# 18_-WIFI_MODULE.net
KiCad netlist of a schematic drawn in Altium Designer
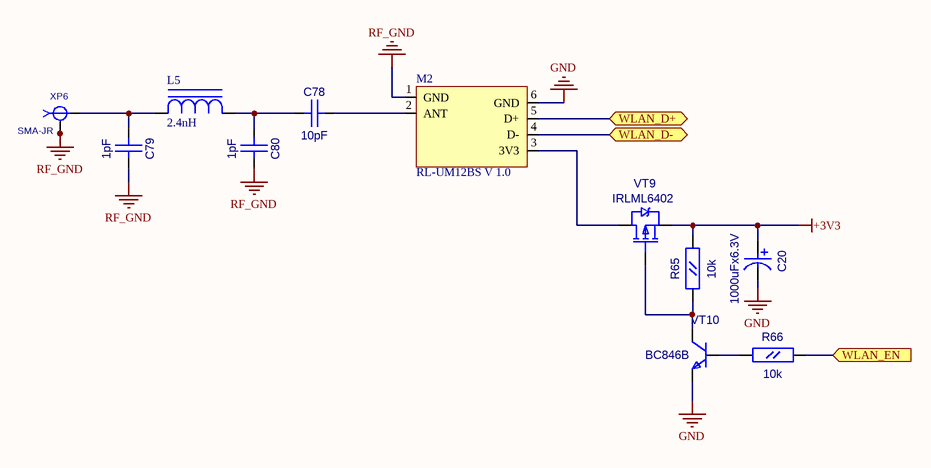
[diagram p0: [18]-WIFI_MODULE.SchDoc]

(export (version "E")
  (design (tool "Eeschema 10.0.6"))
  (components
    (comp (ref "C20")
      (value "1000uFx6.3V")
      (footprint "CC8X3.5")
      (description "Radial capacitor")
      (libsource (lib "fizik_lib (1)") (part "CAP_8mm"))
    )
    (comp (ref "C78")
      (value "10pF")
      (footprint "CC0603")
      (description "CC0603")
      (libsource (lib "gprs_modem_2") (part "CC0603"))
    )
    (comp (ref "C79")
      (value "1pF")
      (footprint "CC0603")
      (description "CC0603")
      (libsource (lib "gprs_modem_2") (part "CC0603"))
    )
    (comp (ref "C80")
      (value "1pF")
      (footprint "CC0603")
      (description "CC0603")
      (libsource (lib "gprs_modem_2") (part "CC0603"))
    )
    (comp (ref "L5")
      (value "2.4nH")
      (footprint "L0402")
      (description "L0402")
      (libsource (lib "gprs_modem_2") (part "L0402"))
    )
    (comp (ref "M2")
      (value "RL-UM12BS V 1.0")
      (footprint "RTL8188_MODULE")
      (libsource (lib "fizik_lib") (part "RTL8188_MODULE"))
    )
    (comp (ref "R65")
      (value "10k")
      (footprint "RC0603")
      (description "RC0603")
      (libsource (lib "gprs_modem_2") (part "RC0603"))
    )
    (comp (ref "R66")
      (value "10k")
      (footprint "RC0603")
      (description "RC0603")
      (libsource (lib "gprs_modem_2") (part "RC0603"))
    )
    (comp (ref "VT9")
      (value "IRLML6402")
      (footprint "SOT-23(123)")
      (description "HEXFET Power MOSFET")
      (libsource (lib "gprs_modem_2") (part "IRLML6402"))
    )
    (comp (ref "VT10")
      (value "BC846B")
      (footprint "SOT-23(123)")
      (description "BC846BLT1")
      (libsource (lib "gprs_modem_2") (part "BC846BLT1"))
    )
    (comp (ref "XP6") (value "SMA-JR") (footprint "SMA-JR") (libsource (lib "fizik_lib") (part "SMA-JR")))
  )
  (nets
    (net (code "1") (name "+3V3") (class "Default")
      (node (ref "C20") (pin "1") (pintype "passive"))
      (node (ref "R65") (pin "2") (pinfunction "B_2") (pintype "passive"))
      (node (ref "VT9") (pin "2") (pinfunction "S_2") (pintype "passive"))
    )
    (net (code "2") (name "/WLAN_D+") (class "Default")
      (node (ref "M2") (pin "5") (pinfunction "D+_5") (pintype "passive"))
    )
    (net (code "3") (name "/WLAN_D-") (class "Default")
      (node (ref "M2") (pin "4") (pinfunction "D-_4") (pintype "passive"))
    )
    (net (code "4") (name "/WLAN_EN") (class "Default")
      (node (ref "R66") (pin "2") (pinfunction "B_2") (pintype "passive"))
    )
    (net (code "5") (name "GND") (class "Default")
      (node (ref "C20") (pin "2") (pintype "passive"))
      (node (ref "M2") (pin "6") (pinfunction "GND_6") (pintype "passive"))
      (node (ref "VT10") (pin "2") (pinfunction "E_2") (pintype "passive"))
    )
    (net (code "6") (name "Net-(C78-A)") (class "Default")
      (node (ref "C78") (pin "1") (pinfunction "A_1") (pintype "passive"))
      (node (ref "C80") (pin "1") (pinfunction "A_1") (pintype "passive"))
      (node (ref "L5") (pin "2") (pinfunction "C_2") (pintype "passive"))
    )
    (net (code "7") (name "Net-(C78-B)") (class "Default")
      (node (ref "C78") (pin "2") (pinfunction "B_2") (pintype "passive"))
      (node (ref "M2") (pin "2") (pinfunction "ANT_2") (pintype "passive"))
    )
    (net (code "8") (name "Net-(C79-A)") (class "Default")
      (node (ref "C79") (pin "1") (pinfunction "A_1") (pintype "passive"))
      (node (ref "L5") (pin "1") (pinfunction "A_1") (pintype "passive"))
      (node (ref "XP6") (pin "1") (pintype "passive"))
    )
    (net (code "9") (name "Net-(M2-3V3)") (class "Default")
      (node (ref "M2") (pin "3") (pinfunction "3V3_3") (pintype "passive"))
      (node (ref "VT9") (pin "3") (pinfunction "D_3") (pintype "passive"))
    )
    (net (code "10") (name "Net-(R65-A)") (class "Default")
      (node (ref "R65") (pin "1") (pinfunction "A_1") (pintype "passive"))
      (node (ref "VT10") (pin "3") (pinfunction "C_3") (pintype "passive"))
      (node (ref "VT9") (pin "1") (pinfunction "G_1") (pintype "passive"))
    )
    (net (code "11") (name "Net-(R66-A)") (class "Default")
      (node (ref "R66") (pin "1") (pinfunction "A_1") (pintype "passive"))
      (node (ref "VT10") (pin "1") (pinfunction "B_1") (pintype "passive"))
    )
    (net (code "12") (name "RF_GND") (class "Default")
      (node (ref "C79") (pin "2") (pinfunction "B_2") (pintype "passive"))
      (node (ref "C80") (pin "2") (pinfunction "B_2") (pintype "passive"))
      (node (ref "M2") (pin "1") (pinfunction "GND_1") (pintype "passive"))
      (node (ref "XP6") (pin "2") (pintype "passive"))
      (node (ref "XP6") (pin "3") (pintype "passive"))
      (node (ref "XP6") (pin "4") (pintype "passive"))
      (node (ref "XP6") (pin "5") (pintype "passive"))
    )
  )
)
